# Mechaduino02.net
KiCad netlist of a schematic drawn in EAGLE
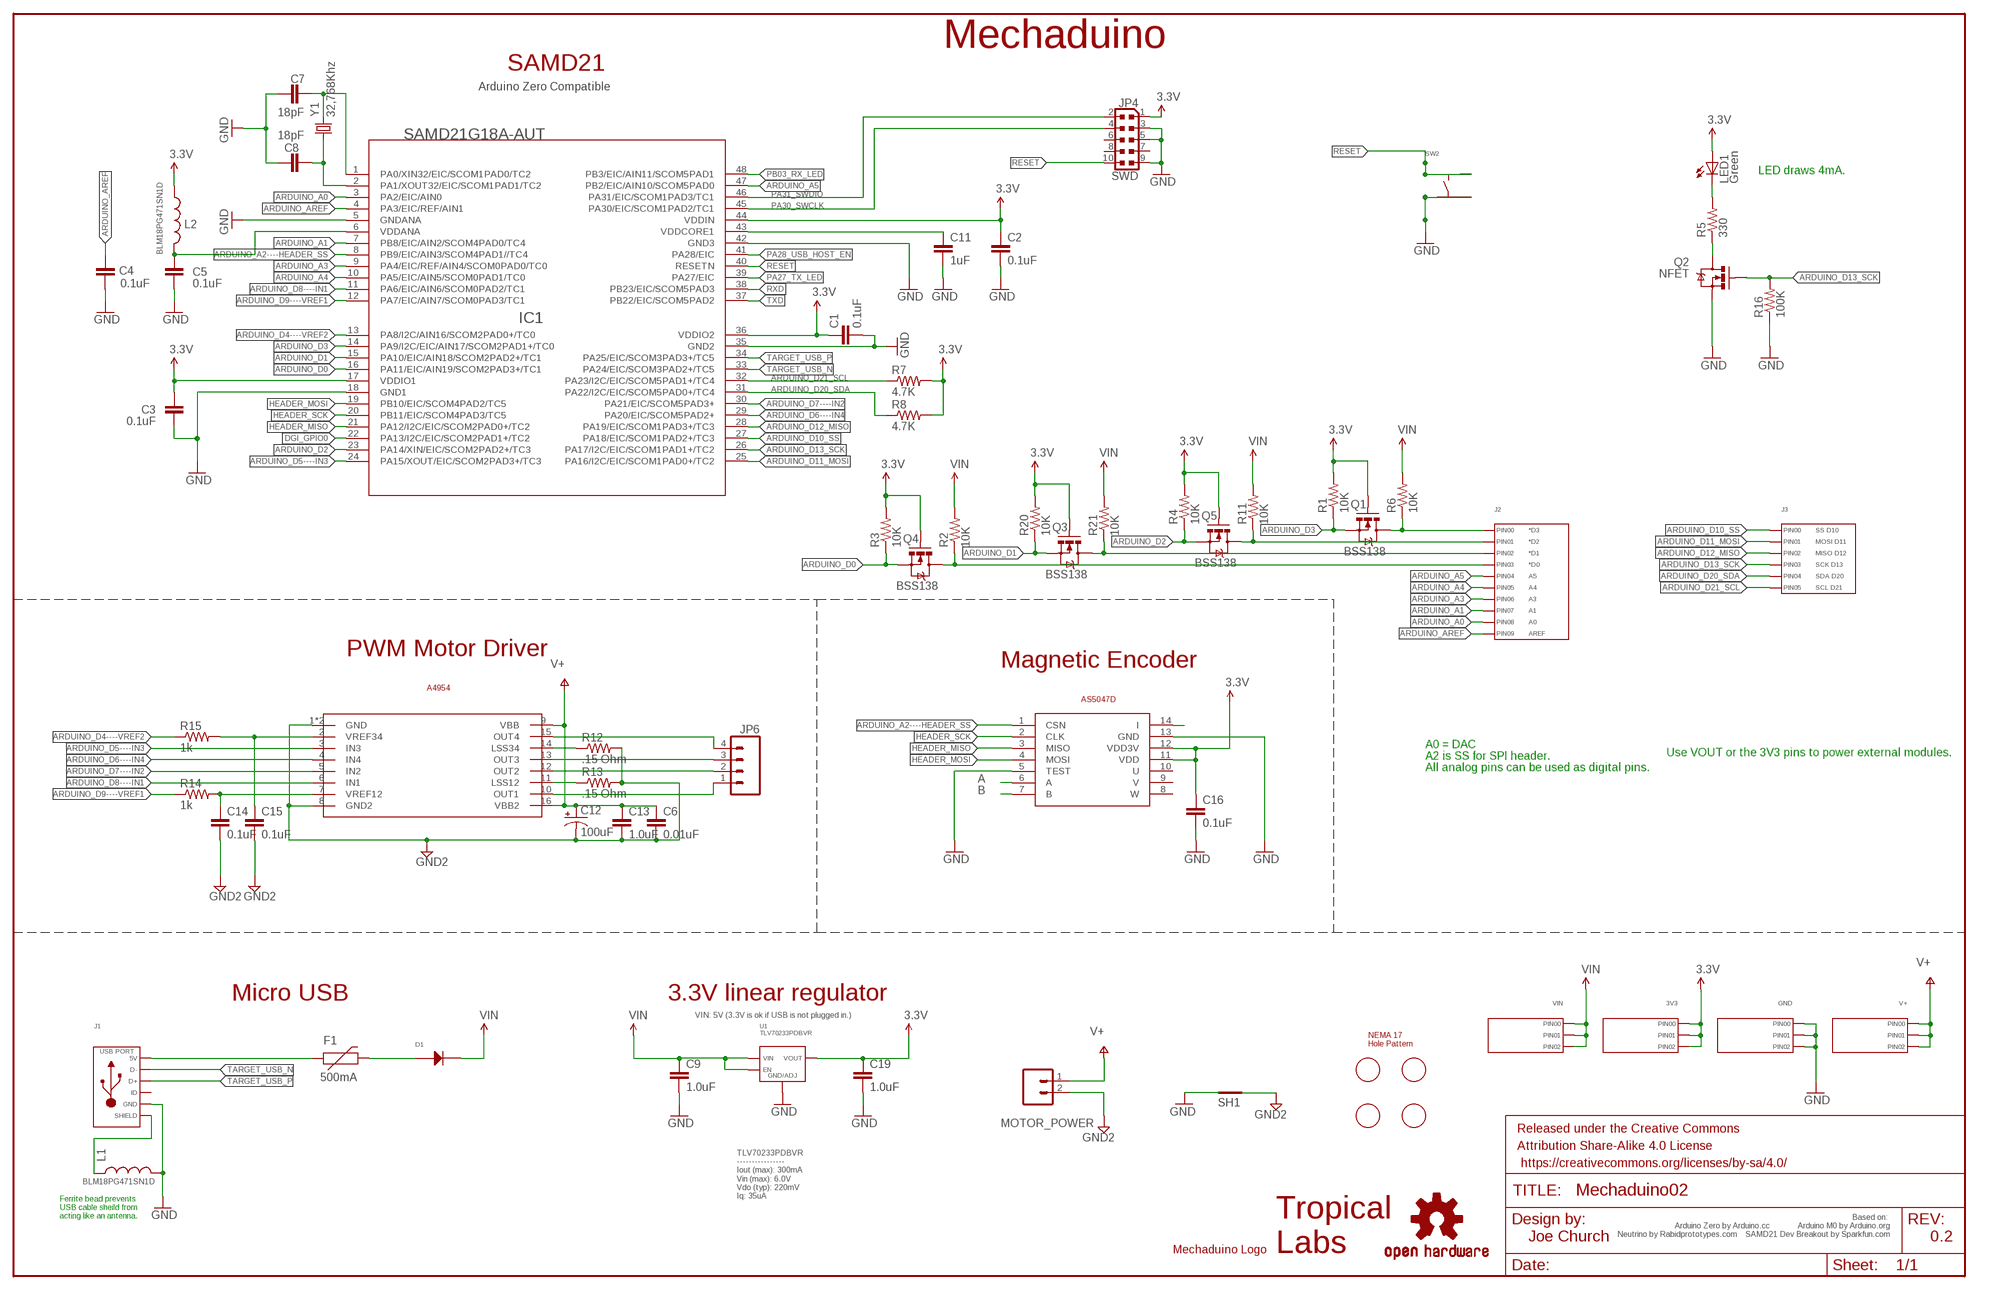
[diagram p0: schematic, sheet 1]

(export (version "E")
  (design (tool "Eeschema 10.0.6"))
  (components
    (comp (ref "3V3")
      (value "HEADER_01X03_PTH_2.54MM")
      (footprint "eagle-import:PTH_2.54MM_01X03")
      (libsource (lib "eagle-import") (part "HEADER_01X03_PTH_2.54MM"))
    )
    (comp (ref "C1")
      (value "0.1uF")
      (footprint "eagle-import:0402-CAP")
      (libsource (lib "eagle-import") (part "CAP0402"))
    )
    (comp (ref "C2")
      (value "0.1uF")
      (footprint "eagle-import:0402-CAP")
      (libsource (lib "eagle-import") (part "CAP0402"))
    )
    (comp (ref "C3")
      (value "0.1uF")
      (footprint "eagle-import:0402-CAP")
      (libsource (lib "eagle-import") (part "CAP0402"))
    )
    (comp (ref "C4")
      (value "0.1uF")
      (footprint "eagle-import:0402-CAP")
      (libsource (lib "eagle-import") (part "CAP0402"))
    )
    (comp (ref "C5")
      (value "0.1uF")
      (footprint "eagle-import:0402-CAP")
      (libsource (lib "eagle-import") (part "CAP0402"))
    )
    (comp (ref "C6")
      (value "0.01uF")
      (footprint "eagle-import:0603-CAP")
      (libsource (lib "eagle-import") (part "CAP0603"))
    )
    (comp (ref "C7")
      (value "18pF")
      (footprint "eagle-import:0603-CAP")
      (libsource (lib "eagle-import") (part "CAP0603"))
    )
    (comp (ref "C8")
      (value "18pF")
      (footprint "eagle-import:0603-CAP")
      (libsource (lib "eagle-import") (part "CAP0603"))
    )
    (comp (ref "C9")
      (value "1.0uF")
      (footprint "eagle-import:0402-CAP")
      (libsource (lib "eagle-import") (part "CAP0402"))
    )
    (comp (ref "C11")
      (value "1uF")
      (footprint "eagle-import:0402-CAP")
      (libsource (lib "eagle-import") (part "CAP0402"))
    )
    (comp (ref "C12")
      (value "100uF")
      (footprint "eagle-import:PANASONIC_D")
      (libsource (lib "eagle-import") (part "CAP_POLD"))
    )
    (comp (ref "C13")
      (value "1.0uF")
      (footprint "eagle-import:0603-CAP")
      (libsource (lib "eagle-import") (part "CAP0603"))
    )
    (comp (ref "C14")
      (value "0.1uF")
      (footprint "eagle-import:0402-CAP")
      (libsource (lib "eagle-import") (part "CAP0402"))
    )
    (comp (ref "C15")
      (value "0.1uF")
      (footprint "eagle-import:0402-CAP")
      (libsource (lib "eagle-import") (part "CAP0402"))
    )
    (comp (ref "C16")
      (value "0.1uF")
      (footprint "eagle-import:0402-CAP")
      (libsource (lib "eagle-import") (part "CAP0402"))
    )
    (comp (ref "C19")
      (value "1.0uF")
      (footprint "eagle-import:0402-CAP")
      (libsource (lib "eagle-import") (part "CAP0402"))
    )
    (comp (ref "D1")
      (value "DIODE_SOD-123")
      (footprint "eagle-import:SOD-123")
      (libsource (lib "eagle-import") (part "DIODE_SOD-123"))
    )
    (comp (ref "F1")
      (value "500mA")
      (footprint "eagle-import:PTC-1206")
      (libsource (lib "eagle-import") (part "PTCSMD"))
    )
    (comp (ref "FRAME1")
      (value "FRAME-LEDGER")
      (footprint "eagle-import:CREATIVE_COMMONS")
      (libsource (lib "eagle-import") (part "FRAME-LEDGER"))
    )
    (comp (ref "GND")
      (value "HEADER_01X03_PTH_2.54MM")
      (footprint "eagle-import:PTH_2.54MM_01X03")
      (libsource (lib "eagle-import") (part "HEADER_01X03_PTH_2.54MM"))
    )
    (comp (ref "IC1")
      (value "SAMD21G18A-AUT")
      (footprint "eagle-import:INTEGRATEDCIRCUITS_TQFP48-7X7")
      (libsource (lib "eagle-import") (part "INTEGRATEDCIRCUITS_1792_SAMD21G18A-AUT"))
    )
    (comp (ref "J1")
      (value "USB_MICRO_RIGHT")
      (footprint "eagle-import:MICROUSB-RIGHT")
      (libsource (lib "eagle-import") (part "USB_MICRO_RIGHT"))
    )
    (comp (ref "J2")
      (value "HEADER_01X10_PTH_2.54MM")
      (footprint "eagle-import:PTH_2.54MM_01X10")
      (fields
        (field (name "LABEL00") "*D3")
        (field (name "LABEL01") "*D2")
        (field (name "LABEL02") "*D1")
        (field (name "LABEL03") "*D0")
        (field (name "LABEL04") "A5")
        (field (name "LABEL05") "A4")
        (field (name "LABEL06") "A3")
        (field (name "LABEL07") "A1")
        (field (name "LABEL08") "A0")
        (field (name "LABEL09") "AREF")
      )
      (libsource (lib "eagle-import") (part "HEADER_01X10_PTH_2.54MM"))
    )
    (comp (ref "J3")
      (value "HEADER_01X06_PTH_2.54MM")
      (footprint "eagle-import:PTH_2.54MM_01X06")
      (fields
        (field (name "LABEL00") "SS D10")
        (field (name "LABEL01") "MOSI D11")
        (field (name "LABEL02") "MISO D12")
        (field (name "LABEL03") "SCK D13")
        (field (name "LABEL04") "SDA D20")
        (field (name "LABEL05") "SCL D21")
      )
      (libsource (lib "eagle-import") (part "HEADER_01X06_PTH_2.54MM"))
    )
    (comp (ref "JP4")
      (value "SWD")
      (footprint "eagle-import:CONNETTORI_PINHEAD-2X5-P127")
      (libsource (lib "eagle-import") (part "CONNETTORI_0171_PH127-205DF055G00A"))
    )
    (comp (ref "JP6")
      (value "M04PTH")
      (footprint "eagle-import:1X04")
      (libsource (lib "eagle-import") (part "M04PTH"))
    )
    (comp (ref "L1")
      (value "BLM18PG471SN1D")
      (footprint "eagle-import:0603-TDK")
      (libsource (lib "eagle-import") (part "INDUCTOR0603-TDK"))
    )
    (comp (ref "L2")
      (value "BLM18PG471SN1D")
      (footprint "eagle-import:0603-TDK")
      (libsource (lib "eagle-import") (part "INDUCTOR0603-TDK"))
    )
    (comp (ref "LED1")
      (value "Green")
      (footprint "eagle-import:CHIPLED_0805")
      (fields (field (name "PART_NUMBER") "KPT-2012YC"))
      (libsource (lib "eagle-import") (part "0044_KPT-2012YC"))
    )
    (comp (ref "LOGO4")
      (value "OSHW-LOGOMOD")
      (footprint "eagle-import:OSHW_LOGO_COPPER_MOD")
      (libsource (lib "eagle-import") (part "OSHW-LOGOMOD"))
    )
    (comp (ref "MOTOR_POWER")
      (value "M025MM")
      (footprint "eagle-import:SCREWTERMINAL-5MM-2")
      (libsource (lib "eagle-import") (part "M025MM"))
    )
    (comp (ref "Q1")
      (value "BSS138")
      (footprint "eagle-import:SOT23-3")
      (libsource (lib "eagle-import") (part "MOSFET-NCHANNELSMD"))
    )
    (comp (ref "Q2")
      (value "NFET")
      (footprint "eagle-import:SOT323")
      (libsource (lib "eagle-import") (part "MOSFET-NCHANNEL2N7002PW"))
    )
    (comp (ref "Q3")
      (value "BSS138")
      (footprint "eagle-import:SOT23-3")
      (libsource (lib "eagle-import") (part "MOSFET-NCHANNELSMD"))
    )
    (comp (ref "Q4")
      (value "BSS138")
      (footprint "eagle-import:SOT23-3")
      (libsource (lib "eagle-import") (part "MOSFET-NCHANNELSMD"))
    )
    (comp (ref "Q5")
      (value "BSS138")
      (footprint "eagle-import:SOT23-3")
      (libsource (lib "eagle-import") (part "MOSFET-NCHANNELSMD"))
    )
    (comp (ref "R1")
      (value "10K")
      (footprint "eagle-import:R0402-VISHAY")
      (libsource (lib "eagle-import") (part "R-US_R0402-VISHAY"))
    )
    (comp (ref "R2")
      (value "10K")
      (footprint "eagle-import:R0402-VISHAY")
      (libsource (lib "eagle-import") (part "R-US_R0402-VISHAY"))
    )
    (comp (ref "R3")
      (value "10K")
      (footprint "eagle-import:R0402-VISHAY")
      (libsource (lib "eagle-import") (part "R-US_R0402-VISHAY"))
    )
    (comp (ref "R4")
      (value "10K")
      (footprint "eagle-import:R0402-VISHAY")
      (libsource (lib "eagle-import") (part "R-US_R0402-VISHAY"))
    )
    (comp (ref "R5")
      (value "330")
      (footprint "eagle-import:R0402-VISHAY")
      (libsource (lib "eagle-import") (part "R-US_R0402-VISHAY"))
    )
    (comp (ref "R6")
      (value "10K")
      (footprint "eagle-import:R0402-VISHAY")
      (libsource (lib "eagle-import") (part "R-US_R0402-VISHAY"))
    )
    (comp (ref "R7")
      (value "4.7K")
      (footprint "eagle-import:R0402-VISHAY")
      (libsource (lib "eagle-import") (part "R-US_R0402-VISHAY"))
    )
    (comp (ref "R8")
      (value "4.7K")
      (footprint "eagle-import:R0402-VISHAY")
      (libsource (lib "eagle-import") (part "R-US_R0402-VISHAY"))
    )
    (comp (ref "R11")
      (value "10K")
      (footprint "eagle-import:R0402-VISHAY")
      (libsource (lib "eagle-import") (part "R-US_R0402-VISHAY"))
    )
    (comp (ref "R12")
      (value ".15 Ohm")
      (footprint "eagle-import:R1206")
      (libsource (lib "eagle-import") (part "R-US_R1206"))
    )
    (comp (ref "R13")
      (value ".15 Ohm")
      (footprint "eagle-import:R1206")
      (libsource (lib "eagle-import") (part "R-US_R1206"))
    )
    (comp (ref "R14")
      (value "1k")
      (footprint "eagle-import:R0402-VISHAY")
      (libsource (lib "eagle-import") (part "R-US_R0402-VISHAY"))
    )
    (comp (ref "R15")
      (value "1k")
      (footprint "eagle-import:R0402-VISHAY")
      (libsource (lib "eagle-import") (part "R-US_R0402-VISHAY"))
    )
    (comp (ref "R16")
      (value "100K")
      (footprint "eagle-import:R0402-VISHAY")
      (libsource (lib "eagle-import") (part "R-US_R0402-VISHAY"))
    )
    (comp (ref "R20")
      (value "10K")
      (footprint "eagle-import:R0402-VISHAY")
      (libsource (lib "eagle-import") (part "R-US_R0402-VISHAY"))
    )
    (comp (ref "R21")
      (value "10K")
      (footprint "eagle-import:R0402-VISHAY")
      (libsource (lib "eagle-import") (part "R-US_R0402-VISHAY"))
    )
    (comp (ref "SH1")
      (value "SHORT-HA5")
      (footprint "eagle-import:SHORT_ALL-50")
      (libsource (lib "eagle-import") (part "SHORT-HA5"))
    )
    (comp (ref "SW2")
      (value "TACT_4.2MM")
      (footprint "eagle-import:TACT4.2MM")
      (libsource (lib "eagle-import") (part "TACT_4.2MM"))
    )
    (comp (ref "U$1")
      (value "AVAGO_DRIVERTHERM")
      (footprint "eagle-import:TSSOP16_THERM")
      (libsource (lib "eagle-import") (part "AVAGO_DRIVERTHERM"))
    )
    (comp (ref "U$2")
      (value "NEMA17_HOLE_PATTERNNEW")
      (footprint "eagle-import:NEMA17_HOLE_PATTERN_2")
      (libsource (lib "eagle-import") (part "NEMA17_HOLE_PATTERNNEW"))
    )
    (comp (ref "U$3")
      (value "TROPICAL_LABS_LOGO_1LOGO3")
      (footprint "eagle-import:LOGO3")
      (libsource (lib "eagle-import") (part "TROPICAL_LABS_LOGO_1LOGO3"))
    )
    (comp (ref "U$4")
      (value "AS5047D")
      (footprint "eagle-import:TSSOP14")
      (libsource (lib "eagle-import") (part "AS5047D"))
    )
    (comp (ref "U$5")
      (value "MECHADUINO_LOGO")
      (footprint "eagle-import:MECHADUINO_LOGO")
      (libsource (lib "eagle-import") (part "MECHADUINO_LOGO"))
    )
    (comp (ref "U1")
      (value "TLV70233PDBVR")
      (footprint "eagle-import:SOT-23-5")
      (libsource (lib "eagle-import") (part "TLV70233PDBVR"))
    )
    (comp (ref "V+")
      (value "HEADER_01X03_PTH_2.54MM")
      (footprint "eagle-import:PTH_2.54MM_01X03")
      (libsource (lib "eagle-import") (part "HEADER_01X03_PTH_2.54MM"))
    )
    (comp (ref "VIN")
      (value "HEADER_01X03_PTH_2.54MM")
      (footprint "eagle-import:PTH_2.54MM_01X03")
      (libsource (lib "eagle-import") (part "HEADER_01X03_PTH_2.54MM"))
    )
    (comp (ref "Y1")
      (value "32,768Khz")
      (footprint "eagle-import:CRYSTAL-SMD-2.0X1.2")
      (libsource (lib "eagle-import") (part "CRYSTAL2012"))
    )
  )
  (nets
    (net (code "1") (name "/A") (class "Default")
      (node (ref "U$4") (pin "6") (pinfunction "A_6") (pintype "bidirectional"))
    )
    (net (code "2") (name "/B") (class "Default")
      (node (ref "U$4") (pin "7") (pinfunction "B_7") (pintype "bidirectional"))
    )
    (net (code "3") (name "/PA30_SWCLK") (class "Default")
      (node (ref "IC1") (pin "45") (pinfunction "PA30/EIC/SCOM1PAD2/TC1_45") (pintype "bidirectional"))
      (node (ref "JP4") (pin "4") (pinfunction "4_4") (pintype "passive"))
    )
    (net (code "4") (name "/PA31_SWDIO") (class "Default")
      (node (ref "IC1") (pin "46") (pinfunction "PA31/EIC/SCOM1PAD3/TC1_46") (pintype "bidirectional"))
      (node (ref "JP4") (pin "2") (pinfunction "2_2") (pintype "passive"))
    )
    (net (code "5") (name "3.3V") (class "Default")
      (node (ref "3V3") (pin "P$1") (pinfunction "PIN0_P$1") (pintype "bidirectional"))
      (node (ref "3V3") (pin "P$2") (pinfunction "PIN1_P$2") (pintype "bidirectional"))
      (node (ref "3V3") (pin "P$3") (pinfunction "PIN2_P$3") (pintype "bidirectional"))
      (node (ref "C1") (pin "1") (pinfunction "1_1") (pintype "passive"))
      (node (ref "C16") (pin "1") (pinfunction "1_1") (pintype "passive"))
      (node (ref "C19") (pin "1") (pinfunction "1_1") (pintype "passive"))
      (node (ref "C2") (pin "1") (pinfunction "1_1") (pintype "passive"))
      (node (ref "C3") (pin "2") (pinfunction "2_2") (pintype "passive"))
      (node (ref "IC1") (pin "17") (pinfunction "VDDIO1_17") (pintype "power_in"))
      (node (ref "IC1") (pin "36") (pinfunction "VDDIO2_36") (pintype "power_in"))
      (node (ref "IC1") (pin "44") (pinfunction "VDDIN_44") (pintype "power_in"))
      (node (ref "JP4") (pin "1") (pinfunction "1_1") (pintype "passive"))
      (node (ref "L2") (pin "1") (pinfunction "1_1") (pintype "passive"))
      (node (ref "LED1") (pin "A") (pinfunction "A_A") (pintype "passive"))
      (node (ref "Q1") (pin "1") (pinfunction "G_1") (pintype "passive"))
      (node (ref "Q3") (pin "1") (pinfunction "G_1") (pintype "passive"))
      (node (ref "Q4") (pin "1") (pinfunction "G_1") (pintype "passive"))
      (node (ref "Q5") (pin "1") (pinfunction "G_1") (pintype "passive"))
      (node (ref "R1") (pin "2") (pinfunction "2_2") (pintype "passive"))
      (node (ref "R20") (pin "2") (pinfunction "2_2") (pintype "passive"))
      (node (ref "R3") (pin "2") (pinfunction "2_2") (pintype "passive"))
      (node (ref "R4") (pin "2") (pinfunction "2_2") (pintype "passive"))
      (node (ref "R7") (pin "2") (pinfunction "2_2") (pintype "passive"))
      (node (ref "R8") (pin "2") (pinfunction "2_2") (pintype "passive"))
      (node (ref "U$4") (pin "11") (pinfunction "VDD_11") (pintype "bidirectional"))
      (node (ref "U$4") (pin "12") (pinfunction "VDD3V_12") (pintype "bidirectional"))
      (node (ref "U1") (pin "P$5") (pinfunction "VOUT_P$5") (pintype "bidirectional"))
    )
    (net (code "6") (name "ARDUINO_A0") (class "Default")
      (node (ref "IC1") (pin "3") (pinfunction "PA2/EIC/AIN0_3") (pintype "bidirectional"))
      (node (ref "J2") (pin "P$9") (pinfunction "PIN8_P$9") (pintype "bidirectional"))
    )
    (net (code "7") (name "ARDUINO_A1") (class "Default")
      (node (ref "IC1") (pin "7") (pinfunction "PB8/EIC/AIN2/SCOM4PAD0/TC4_7") (pintype "bidirectional"))
      (node (ref "J2") (pin "P$8") (pinfunction "PIN7_P$8") (pintype "bidirectional"))
    )
    (net (code "8") (name "ARDUINO_A2----HEADER_SS") (class "Default")
      (node (ref "IC1") (pin "8") (pinfunction "PB9/EIC/AIN3/SCOM4PAD1//TC4_8") (pintype "bidirectional"))
      (node (ref "U$4") (pin "1") (pinfunction "CSN_1") (pintype "bidirectional"))
    )
    (net (code "9") (name "ARDUINO_A3") (class "Default")
      (node (ref "IC1") (pin "9") (pinfunction "PA4/EIC/REF/AIN4/SCOM0PAD0/TC0_9") (pintype "bidirectional"))
      (node (ref "J2") (pin "P$7") (pinfunction "PIN6_P$7") (pintype "bidirectional"))
    )
    (net (code "10") (name "ARDUINO_A4") (class "Default")
      (node (ref "IC1") (pin "10") (pinfunction "PA5/EIC/AIN5/SCOM0PAD1/TC0_10") (pintype "bidirectional"))
      (node (ref "J2") (pin "P$6") (pinfunction "PIN5_P$6") (pintype "bidirectional"))
    )
    (net (code "11") (name "ARDUINO_A5") (class "Default")
      (node (ref "IC1") (pin "47") (pinfunction "PB2/EIC/AIN10/SCOM5PAD0_47") (pintype "bidirectional"))
      (node (ref "J2") (pin "P$5") (pinfunction "PIN4_P$5") (pintype "bidirectional"))
    )
    (net (code "12") (name "ARDUINO_AREF") (class "Default")
      (node (ref "C4") (pin "1") (pinfunction "1_1") (pintype "passive"))
      (node (ref "IC1") (pin "4") (pinfunction "PA3/EIC/REF/AIN1_4") (pintype "bidirectional"))
      (node (ref "J2") (pin "P$10") (pinfunction "PIN9_P$10") (pintype "bidirectional"))
    )
    (net (code "13") (name "ARDUINO_D0") (class "Default")
      (node (ref "IC1") (pin "16") (pinfunction "PA11/EIC/AIN19/SCOM2PAD3+/TC1_16") (pintype "bidirectional"))
      (node (ref "Q4") (pin "2") (pinfunction "S_2") (pintype "passive"))
      (node (ref "R3") (pin "1") (pinfunction "1_1") (pintype "passive"))
    )
    (net (code "14") (name "ARDUINO_D1") (class "Default")
      (node (ref "IC1") (pin "15") (pinfunction "PA10/EIC/AIN18/SCOM2PAD2+/TC1_15") (pintype "bidirectional"))
      (node (ref "Q3") (pin "2") (pinfunction "S_2") (pintype "passive"))
      (node (ref "R20") (pin "1") (pinfunction "1_1") (pintype "passive"))
    )
    (net (code "15") (name "ARDUINO_D2") (class "Default")
      (node (ref "IC1") (pin "23") (pinfunction "PA14/XIN/EIC/SCOM2PAD2+/TC3_23") (pintype "bidirectional"))
      (node (ref "Q5") (pin "2") (pinfunction "S_2") (pintype "passive"))
      (node (ref "R4") (pin "1") (pinfunction "1_1") (pintype "passive"))
    )
    (net (code "16") (name "ARDUINO_D3") (class "Default")
      (node (ref "IC1") (pin "14") (pinfunction "PA9/I2C/EIC/AIN17/SCOM2PAD1+/TC0_14") (pintype "bidirectional"))
      (node (ref "Q1") (pin "2") (pinfunction "S_2") (pintype "passive"))
      (node (ref "R1") (pin "1") (pinfunction "1_1") (pintype "passive"))
    )
    (net (code "17") (name "ARDUINO_D4----VREF2") (class "Default")
      (node (ref "IC1") (pin "13") (pinfunction "PA8/I2C/AIN16/SCOM2PAD0+/TC0_13") (pintype "bidirectional"))
      (node (ref "R15") (pin "1") (pinfunction "1_1") (pintype "passive"))
    )
    (net (code "18") (name "ARDUINO_D5----IN3") (class "Default")
      (node (ref "IC1") (pin "24") (pinfunction "PA15/XOUT/EIC/SCOM2PAD3+/TC3_24") (pintype "bidirectional"))
      (node (ref "U$1") (pin "3") (pinfunction "IN3_3") (pintype "bidirectional"))
    )
    (net (code "19") (name "ARDUINO_D6----IN4") (class "Default")
      (node (ref "IC1") (pin "29") (pinfunction "PA20/EIC/SCOM5PAD2+_29") (pintype "bidirectional"))
      (node (ref "U$1") (pin "4") (pinfunction "IN4_4") (pintype "bidirectional"))
    )
    (net (code "20") (name "ARDUINO_D7----IN2") (class "Default")
      (node (ref "IC1") (pin "30") (pinfunction "PA21/EIC/SCOM5PAD3+_30") (pintype "bidirectional"))
      (node (ref "U$1") (pin "5") (pinfunction "IN2_5") (pintype "bidirectional"))
    )
    (net (code "21") (name "ARDUINO_D8----IN1") (class "Default")
      (node (ref "IC1") (pin "11") (pinfunction "PA6/EIC/AIN6/SCOM0PAD2/TC1_11") (pintype "bidirectional"))
      (node (ref "U$1") (pin "6") (pinfunction "IN1_6") (pintype "bidirectional"))
    )
    (net (code "22") (name "ARDUINO_D9----VREF1") (class "Default")
      (node (ref "IC1") (pin "12") (pinfunction "PA7/EIC/AIN7/SCOM0PAD3/TC1_12") (pintype "bidirectional"))
      (node (ref "R14") (pin "1") (pinfunction "1_1") (pintype "passive"))
    )
    (net (code "23") (name "ARDUINO_D10_SS") (class "Default")
      (node (ref "IC1") (pin "27") (pinfunction "PA18/EIC/SCOM1PAD2+/TC3_27") (pintype "bidirectional"))
      (node (ref "J3") (pin "P$1") (pinfunction "PIN0_P$1") (pintype "bidirectional"))
    )
    (net (code "24") (name "ARDUINO_D11_MOSI") (class "Default")
      (node (ref "IC1") (pin "25") (pinfunction "PA16/I2C/EIC/SCOM1PAD0+/TC2_25") (pintype "bidirectional"))
      (node (ref "J3") (pin "P$2") (pinfunction "PIN1_P$2") (pintype "bidirectional"))
    )
    (net (code "25") (name "ARDUINO_D12_MISO") (class "Default")
      (node (ref "IC1") (pin "28") (pinfunction "PA19/EIC/SCOM1PAD3+/TC3_28") (pintype "bidirectional"))
      (node (ref "J3") (pin "P$3") (pinfunction "PIN2_P$3") (pintype "bidirectional"))
    )
    (net (code "26") (name "ARDUINO_D13_SCK") (class "Default")
      (node (ref "IC1") (pin "26") (pinfunction "PA17/I2C/EIC/SCOM1PAD1+/TC2_26") (pintype "bidirectional"))
      (node (ref "J3") (pin "P$4") (pinfunction "PIN3_P$4") (pintype "bidirectional"))
      (node (ref "Q2") (pin "1") (pinfunction "G_1") (pintype "passive"))
      (node (ref "R16") (pin "2") (pinfunction "2_2") (pintype "passive"))
    )
    (net (code "27") (name "ARDUINO_D20_SDA") (class "Default")
      (node (ref "IC1") (pin "31") (pinfunction "PA22/I2C/EIC/SCOM5PAD0+/TC4_31") (pintype "bidirectional"))
      (node (ref "J3") (pin "P$5") (pinfunction "PIN4_P$5") (pintype "bidirectional"))
      (node (ref "R8") (pin "1") (pinfunction "1_1") (pintype "passive"))
    )
    (net (code "28") (name "ARDUINO_D21_SCL") (class "Default")
      (node (ref "IC1") (pin "32") (pinfunction "PA23/I2C/EIC/SCOM5PAD1+/TC4_32") (pintype "bidirectional"))
      (node (ref "J3") (pin "P$6") (pinfunction "PIN5_P$6") (pintype "bidirectional"))
      (node (ref "R7") (pin "1") (pinfunction "1_1") (pintype "passive"))
    )
    (net (code "29") (name "DGI_GPIO0") (class "Default")
      (node (ref "IC1") (pin "22") (pinfunction "PA13/I2C/EIC/SCOM2PAD1+/TC2_22") (pintype "bidirectional"))
    )
    (net (code "30") (name "GND") (class "Default")
      (node (ref "C1") (pin "2") (pinfunction "2_2") (pintype "passive"))
      (node (ref "C11") (pin "2") (pinfunction "2_2") (pintype "passive"))
      (node (ref "C16") (pin "2") (pinfunction "2_2") (pintype "passive"))
      (node (ref "C19") (pin "2") (pinfunction "2_2") (pintype "passive"))
      (node (ref "C2") (pin "2") (pinfunction "2_2") (pintype "passive"))
      (node (ref "C3") (pin "1") (pinfunction "1_1") (pintype "passive"))
      (node (ref "C4") (pin "2") (pinfunction "2_2") (pintype "passive"))
      (node (ref "C5") (pin "2") (pinfunction "2_2") (pintype "passive"))
      (node (ref "C7") (pin "1") (pinfunction "1_1") (pintype "passive"))
      (node (ref "C8") (pin "1") (pinfunction "1_1") (pintype "passive"))
      (node (ref "C9") (pin "2") (pinfunction "2_2") (pintype "passive"))
      (node (ref "GND") (pin "P$1") (pinfunction "PIN0_P$1") (pintype "bidirectional"))
      (node (ref "GND") (pin "P$2") (pinfunction "PIN1_P$2") (pintype "bidirectional"))
      (node (ref "GND") (pin "P$3") (pinfunction "PIN2_P$3") (pintype "bidirectional"))
      (node (ref "IC1") (pin "18") (pinfunction "GND1_18") (pintype "power_in"))
      (node (ref "IC1") (pin "35") (pinfunction "GND2_35") (pintype "power_in"))
      (node (ref "IC1") (pin "42") (pinfunction "GND3_42") (pintype "power_in"))
      (node (ref "IC1") (pin "5") (pinfunction "GNDANA_5") (pintype "power_in"))
      (node (ref "J1") (pin "5") (pinfunction "GND_5") (pintype "power_in"))
      (node (ref "JP4") (pin "3") (pinfunction "3_3") (pintype "passive"))
      (node (ref "JP4") (pin "5") (pinfunction "5_5") (pintype "passive"))
      (node (ref "JP4") (pin "9") (pinfunction "9_9") (pintype "passive"))
      (node (ref "L1") (pin "2") (pinfunction "2_2") (pintype "passive"))
      (node (ref "Q2") (pin "2") (pinfunction "S_2") (pintype "passive"))
      (node (ref "R16") (pin "1") (pinfunction "1_1") (pintype "passive"))
      (node (ref "SH1") (pin "2") (pinfunction "P$2_2") (pintype "bidirectional"))
      (node (ref "SW2") (pin "P$3") (pinfunction "P$3_P$3") (pintype "bidirectional"))
      (node (ref "SW2") (pin "P$4") (pinfunction "P$4_P$4") (pintype "bidirectional"))
      (node (ref "U$4") (pin "13") (pinfunction "GND_13") (pintype "bidirectional"))
      (node (ref "U$4") (pin "5") (pinfunction "TEST_5") (pintype "bidirectional"))
      (node (ref "U1") (pin "P$2") (pinfunction "GND/ADJ_P$2") (pintype "bidirectional"))
    )
    (net (code "31") (name "GND2") (class "Default")
      (node (ref "C12") (pin "-") (pinfunction "-_-") (pintype "passive"))
      (node (ref "C13") (pin "2") (pinfunction "2_2") (pintype "passive"))
      (node (ref "C14") (pin "2") (pinfunction "2_2") (pintype "passive"))
      (node (ref "C15") (pin "2") (pinfunction "2_2") (pintype "passive"))
      (node (ref "C6") (pin "2") (pinfunction "2_2") (pintype "passive"))
      (node (ref "MOTOR_POWER") (pin "2") (pinfunction "2_2") (pintype "passive"))
      (node (ref "R12") (pin "2") (pinfunction "2_2") (pintype "passive"))
      (node (ref "R13") (pin "2") (pinfunction "2_2") (pintype "passive"))
      (node (ref "SH1") (pin "1") (pinfunction "P$1_1") (pintype "bidirectional"))
      (node (ref "U$1") (pin "1") (pinfunction "GND_1") (pintype "bidirectional"))
      (node (ref "U$1") (pin "8") (pinfunction "GND2_8") (pintype "bidirectional"))
      (node (ref "U$1") (pin "P$1") (pinfunction "GND_P$1") (pintype "bidirectional"))
    )
    (net (code "32") (name "HEADER_MISO") (class "Default")
      (node (ref "IC1") (pin "21") (pinfunction "PA12/I2C/EIC/SCOM2PAD0+/TC2_21") (pintype "bidirectional"))
      (node (ref "U$4") (pin "3") (pinfunction "MISO_3") (pintype "bidirectional"))
    )
    (net (code "33") (name "HEADER_MOSI") (class "Default")
      (node (ref "IC1") (pin "19") (pinfunction "PB10/EIC/SCOM4PAD2/TC5_19") (pintype "bidirectional"))
      (node (ref "U$4") (pin "4") (pinfunction "MOSI_4") (pintype "bidirectional"))
    )
    (net (code "34") (name "HEADER_SCK") (class "Default")
      (node (ref "IC1") (pin "20") (pinfunction "PB11/EIC/SCOM4PAD3/TC5_20") (pintype "bidirectional"))
      (node (ref "U$4") (pin "2") (pinfunction "CLK_2") (pintype "bidirectional"))
    )
    (net (code "35") (name "Net-(D1-PadANODE)") (class "Default")
      (node (ref "D1") (pin "ANODE") (pinfunction "ANODE_ANODE") (pintype "bidirectional"))
      (node (ref "F1") (pin "2") (pinfunction "2_2") (pintype "bidirectional"))
    )
    (net (code "36") (name "Net-(IC1-PA0{slash}XIN32{slash}EIC{slash}SCOM1PAD0{slash}TC2)") (class "Default")
      (node (ref "C7") (pin "2") (pinfunction "2_2") (pintype "passive"))
      (node (ref "IC1") (pin "1") (pinfunction "PA0/XIN32/EIC/SCOM1PAD0/TC2_1") (pintype "bidirectional"))
      (node (ref "Y1") (pin "2") (pinfunction "2_2") (pintype "passive"))
    )
    (net (code "37") (name "Net-(IC1-PA1{slash}XOUT32{slash}EIC{slash}SCOM1PAD1{slash}TC2)") (class "Default")
      (node (ref "C8") (pin "2") (pinfunction "2_2") (pintype "passive"))
      (node (ref "IC1") (pin "2") (pinfunction "PA1/XOUT32/EIC/SCOM1PAD1/TC2_2") (pintype "bidirectional"))
      (node (ref "Y1") (pin "1") (pinfunction "1_1") (pintype "passive"))
    )
    (net (code "38") (name "Net-(IC1-VDDANA)") (class "Default")
      (node (ref "C5") (pin "1") (pinfunction "1_1") (pintype "passive"))
      (node (ref "IC1") (pin "6") (pinfunction "VDDANA_6") (pintype "power_in"))
      (node (ref "L2") (pin "2") (pinfunction "2_2") (pintype "passive"))
    )
    (net (code "39") (name "Net-(IC1-VDDCORE1)") (class "Default")
      (node (ref "C11") (pin "1") (pinfunction "1_1") (pintype "passive"))
      (node (ref "IC1") (pin "43") (pinfunction "VDDCORE1_43") (pintype "input"))
    )
    (net (code "40") (name "Net-(J1-5V)") (class "Default")
      (node (ref "F1") (pin "1") (pinfunction "1_1") (pintype "bidirectional"))
      (node (ref "J1") (pin "1") (pinfunction "5V_1") (pintype "power_in"))
    )
    (net (code "41") (name "Net-(J1-SLD-PadS1)") (class "Default")
      (node (ref "J1") (pin "S1") (pinfunction "SLD_S1") (pintype "power_in"))
      (node (ref "J1") (pin "S2") (pinfunction "SLD_S2") (pintype "power_in"))
      (node (ref "J1") (pin "S3") (pinfunction "SLD_S3") (pintype "power_in"))
      (node (ref "J1") (pin "S4") (pinfunction "SLD_S4") (pintype "power_in"))
      (node (ref "J1") (pin "S5") (pinfunction "SLD_S5") (pintype "power_in"))
      (node (ref "J1") (pin "S6") (pinfunction "SLD_S6") (pintype "power_in"))
      (node (ref "J1") (pin "S7") (pinfunction "SLD_S7") (pintype "power_in"))
      (node (ref "J1") (pin "S8") (pinfunction "SLD_S8") (pintype "power_in"))
      (node (ref "L1") (pin "1") (pinfunction "1_1") (pintype "passive"))
    )
    (net (code "42") (name "Net-(J2-PIN0)") (class "Default")
      (node (ref "J2") (pin "P$1") (pinfunction "PIN0_P$1") (pintype "bidirectional"))
      (node (ref "Q1") (pin "3") (pinfunction "D_3") (pintype "passive"))
      (node (ref "R6") (pin "1") (pinfunction "1_1") (pintype "passive"))
    )
    (net (code "43") (name "Net-(J2-PIN1)") (class "Default")
      (node (ref "J2") (pin "P$2") (pinfunction "PIN1_P$2") (pintype "bidirectional"))
      (node (ref "Q5") (pin "3") (pinfunction "D_3") (pintype "passive"))
      (node (ref "R11") (pin "1") (pinfunction "1_1") (pintype "passive"))
    )
    (net (code "44") (name "Net-(J2-PIN2)") (class "Default")
      (node (ref "J2") (pin "P$3") (pinfunction "PIN2_P$3") (pintype "bidirectional"))
      (node (ref "Q3") (pin "3") (pinfunction "D_3") (pintype "passive"))
      (node (ref "R21") (pin "1") (pinfunction "1_1") (pintype "passive"))
    )
    (net (code "45") (name "Net-(J2-PIN3)") (class "Default")
      (node (ref "J2") (pin "P$4") (pinfunction "PIN3_P$4") (pintype "bidirectional"))
      (node (ref "Q4") (pin "3") (pinfunction "D_3") (pintype "passive"))
      (node (ref "R2") (pin "1") (pinfunction "1_1") (pintype "passive"))
    )
    (net (code "46") (name "Net-(LED1-PadC)") (class "Default")
      (node (ref "LED1") (pin "C") (pinfunction "C_C") (pintype "passive"))
      (node (ref "R5") (pin "2") (pinfunction "2_2") (pintype "passive"))
    )
    (net (code "47") (name "Net-(Q2-D)") (class "Default")
      (node (ref "Q2") (pin "3") (pinfunction "D_3") (pintype "passive"))
      (node (ref "R5") (pin "1") (pinfunction "1_1") (pintype "passive"))
    )
    (net (code "48") (name "Net-(U$1-LSS12)") (class "Default")
      (node (ref "R13") (pin "1") (pinfunction "1_1") (pintype "passive"))
      (node (ref "U$1") (pin "11") (pinfunction "LSS12_11") (pintype "bidirectional"))
    )
    (net (code "49") (name "Net-(U$1-LSS34)") (class "Default")
      (node (ref "R12") (pin "1") (pinfunction "1_1") (pintype "passive"))
      (node (ref "U$1") (pin "14") (pinfunction "LSS34_14") (pintype "bidirectional"))
    )
    (net (code "50") (name "Net-(U$1-OUT1)") (class "Default")
      (node (ref "JP6") (pin "1") (pinfunction "1_1") (pintype "passive"))
      (node (ref "U$1") (pin "10") (pinfunction "OUT1_10") (pintype "bidirectional"))
    )
    (net (code "51") (name "Net-(U$1-OUT2)") (class "Default")
      (node (ref "JP6") (pin "2") (pinfunction "2_2") (pintype "passive"))
      (node (ref "U$1") (pin "12") (pinfunction "OUT2_12") (pintype "bidirectional"))
    )
    (net (code "52") (name "Net-(U$1-OUT3)") (class "Default")
      (node (ref "JP6") (pin "3") (pinfunction "3_3") (pintype "passive"))
      (node (ref "U$1") (pin "13") (pinfunction "OUT3_13") (pintype "bidirectional"))
    )
    (net (code "53") (name "Net-(U$1-OUT4)") (class "Default")
      (node (ref "JP6") (pin "4") (pinfunction "4_4") (pintype "passive"))
      (node (ref "U$1") (pin "15") (pinfunction "OUT4_15") (pintype "bidirectional"))
    )
    (net (code "54") (name "Net-(U$1-VREF12)") (class "Default")
      (node (ref "C14") (pin "1") (pinfunction "1_1") (pintype "passive"))
      (node (ref "R14") (pin "2") (pinfunction "2_2") (pintype "passive"))
      (node (ref "U$1") (pin "7") (pinfunction "VREF12_7") (pintype "bidirectional"))
    )
    (net (code "55") (name "Net-(U$1-VREF34)") (class "Default")
      (node (ref "C15") (pin "1") (pinfunction "1_1") (pintype "passive"))
      (node (ref "R15") (pin "2") (pinfunction "2_2") (pintype "passive"))
      (node (ref "U$1") (pin "2") (pinfunction "VREF34_2") (pintype "bidirectional"))
    )
    (net (code "56") (name "PA27_TX_LED") (class "Default")
      (node (ref "IC1") (pin "39") (pinfunction "PA27/EIC_39") (pintype "bidirectional"))
    )
    (net (code "57") (name "PA28_USB_HOST_EN") (class "Default")
      (node (ref "IC1") (pin "41") (pinfunction "PA28/EIC_41") (pintype "bidirectional"))
    )
    (net (code "58") (name "PB03_RX_LED") (class "Default")
      (node (ref "IC1") (pin "48") (pinfunction "PB3/EIC/AIN11/SCOM5PAD1_48") (pintype "bidirectional"))
    )
    (net (code "59") (name "RESET") (class "Default")
      (node (ref "IC1") (pin "40") (pinfunction "RESETN_40") (pintype "bidirectional"))
      (node (ref "JP4") (pin "10") (pinfunction "10_10") (pintype "passive"))
      (node (ref "SW2") (pin "P$1") (pinfunction "P$1_P$1") (pintype "bidirectional"))
      (node (ref "SW2") (pin "P$2") (pinfunction "P$2_P$2") (pintype "bidirectional"))
    )
    (net (code "60") (name "RXD") (class "Default")
      (node (ref "IC1") (pin "38") (pinfunction "PB23/EIC/SCOM5PAD3_38") (pintype "bidirectional"))
    )
    (net (code "61") (name "TARGET_USB_N") (class "Default")
      (node (ref "IC1") (pin "33") (pinfunction "PA24/EIC/SCOM3PAD2+/TC5_33") (pintype "bidirectional"))
      (node (ref "J1") (pin "2") (pinfunction "D-_2") (pintype "bidirectional"))
    )
    (net (code "62") (name "TARGET_USB_P") (class "Default")
      (node (ref "IC1") (pin "34") (pinfunction "PA25/EIC/SCOM3PAD3+/TC5_34") (pintype "bidirectional"))
      (node (ref "J1") (pin "3") (pinfunction "D+_3") (pintype "bidirectional"))
    )
    (net (code "63") (name "TXD") (class "Default")
      (node (ref "IC1") (pin "37") (pinfunction "PB22/EIC/SCOM5PAD2_37") (pintype "bidirectional"))
    )
    (net (code "64") (name "V+") (class "Default")
      (node (ref "C12") (pin "+") (pinfunction "+_+") (pintype "passive"))
      (node (ref "C13") (pin "1") (pinfunction "1_1") (pintype "passive"))
      (node (ref "C6") (pin "1") (pinfunction "1_1") (pintype "passive"))
      (node (ref "MOTOR_POWER") (pin "1") (pinfunction "1_1") (pintype "passive"))
      (node (ref "U$1") (pin "16") (pinfunction "VBB2_16") (pintype "bidirectional"))
      (node (ref "U$1") (pin "9") (pinfunction "VBB_9") (pintype "bidirectional"))
      (node (ref "V+") (pin "P$1") (pinfunction "PIN0_P$1") (pintype "bidirectional"))
      (node (ref "V+") (pin "P$2") (pinfunction "PIN1_P$2") (pintype "bidirectional"))
      (node (ref "V+") (pin "P$3") (pinfunction "PIN2_P$3") (pintype "bidirectional"))
    )
    (net (code "65") (name "VIN") (class "Default")
      (node (ref "C9") (pin "1") (pinfunction "1_1") (pintype "passive"))
      (node (ref "D1") (pin "CATHODE") (pinfunction "CATHODE_CATHODE") (pintype "bidirectional"))
      (node (ref "R11") (pin "2") (pinfunction "2_2") (pintype "passive"))
      (node (ref "R2") (pin "2") (pinfunction "2_2") (pintype "passive"))
      (node (ref "R21") (pin "2") (pinfunction "2_2") (pintype "passive"))
      (node (ref "R6") (pin "2") (pinfunction "2_2") (pintype "passive"))
      (node (ref "U1") (pin "P$1") (pinfunction "VIN_P$1") (pintype "bidirectional"))
      (node (ref "U1") (pin "P$3") (pinfunction "EN_P$3") (pintype "bidirectional"))
      (node (ref "VIN") (pin "P$1") (pinfunction "PIN0_P$1") (pintype "bidirectional"))
      (node (ref "VIN") (pin "P$2") (pinfunction "PIN1_P$2") (pintype "bidirectional"))
      (node (ref "VIN") (pin "P$3") (pinfunction "PIN2_P$3") (pintype "bidirectional"))
    )
    (net (code "66") (name "unconnected-(J1-ID-Pad4)") (class "Default")
      (node (ref "J1") (pin "4") (pinfunction "ID_4") (pintype "bidirectional"))
    )
    (net (code "67") (name "unconnected-(JP4-Pad6)") (class "Default")
      (node (ref "JP4") (pin "6") (pinfunction "6_6") (pintype "passive"))
    )
    (net (code "68") (name "unconnected-(JP4-Pad7)") (class "Default")
      (node (ref "JP4") (pin "7") (pinfunction "7_7") (pintype "passive"))
    )
    (net (code "69") (name "unconnected-(JP4-Pad8)") (class "Default")
      (node (ref "JP4") (pin "8") (pinfunction "8_8") (pintype "passive"))
    )
    (net (code "70") (name "unconnected-(U$4-I-Pad14)") (class "Default")
      (node (ref "U$4") (pin "14") (pinfunction "I_14") (pintype "bidirectional"))
    )
    (net (code "71") (name "unconnected-(U$4-U-Pad10)") (class "Default")
      (node (ref "U$4") (pin "10") (pinfunction "U_10") (pintype "bidirectional"))
    )
    (net (code "72") (name "unconnected-(U$4-V-Pad9)") (class "Default")
      (node (ref "U$4") (pin "9") (pinfunction "V_9") (pintype "bidirectional"))
    )
    (net (code "73") (name "unconnected-(U$4-W-Pad8)") (class "Default")
      (node (ref "U$4") (pin "8") (pinfunction "W_8") (pintype "bidirectional"))
    )
  )
)
